# relayboard.net
KiCad netlist of a schematic drawn in EAGLE
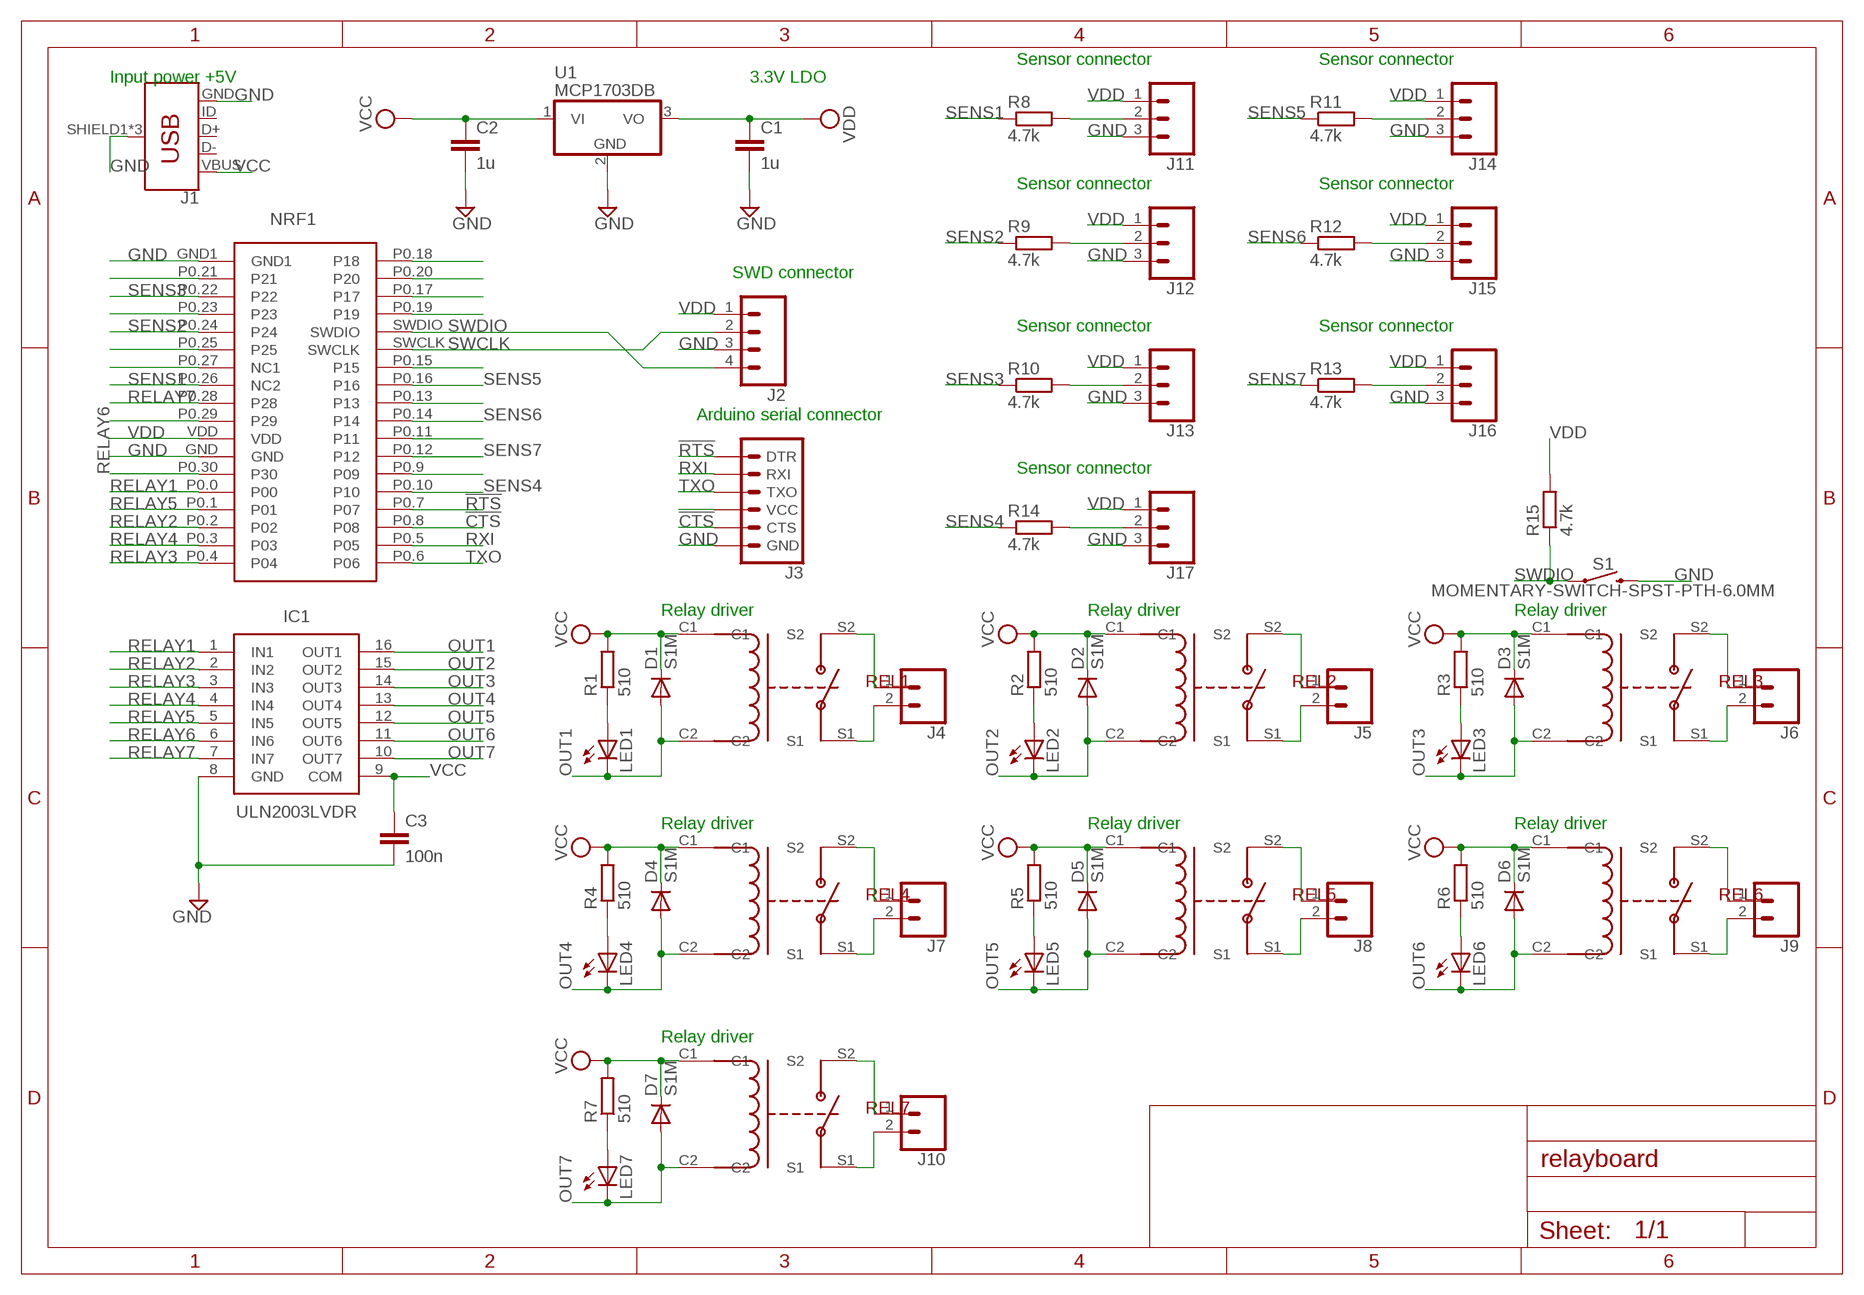
[diagram p0: schematic, sheet 1]

(export (version "E")
  (design (tool "Eeschema 10.0.6"))
  (components
    (comp (ref "C1")
      (value "1u")
      (footprint "eagle-import:C0805")
      (libsource (lib "eagle-import") (part "C-EUC0805"))
    )
    (comp (ref "C2")
      (value "1u")
      (footprint "eagle-import:C0805")
      (libsource (lib "eagle-import") (part "C-EUC0805"))
    )
    (comp (ref "C3")
      (value "100n")
      (footprint "eagle-import:C0805")
      (libsource (lib "eagle-import") (part "C-EUC0805"))
    )
    (comp (ref "D1")
      (value "S1M")
      (footprint "eagle-import:SMA")
      (libsource (lib "eagle-import") (part "S1M"))
    )
    (comp (ref "D2")
      (value "S1M")
      (footprint "eagle-import:SMA")
      (libsource (lib "eagle-import") (part "S1M"))
    )
    (comp (ref "D3")
      (value "S1M")
      (footprint "eagle-import:SMA")
      (libsource (lib "eagle-import") (part "S1M"))
    )
    (comp (ref "D4")
      (value "S1M")
      (footprint "eagle-import:SMA")
      (libsource (lib "eagle-import") (part "S1M"))
    )
    (comp (ref "D5")
      (value "S1M")
      (footprint "eagle-import:SMA")
      (libsource (lib "eagle-import") (part "S1M"))
    )
    (comp (ref "D6")
      (value "S1M")
      (footprint "eagle-import:SMA")
      (libsource (lib "eagle-import") (part "S1M"))
    )
    (comp (ref "D7")
      (value "S1M")
      (footprint "eagle-import:SMA")
      (libsource (lib "eagle-import") (part "S1M"))
    )
    (comp (ref "IC1")
      (value "ULN2003LVDR")
      (footprint "eagle-import:SOIC127P600X175-16N")
      (fields (field (name "RS_PART_NUMBER") "8095475"))
      (libsource (lib "eagle-import") (part "ULN2003LVDR"))
    )
    (comp (ref "J1")
      (value "USB_MICRO-B_FEMALE-SMT")
      (footprint "eagle-import:USB-B-MICRO-SMD")
      (libsource (lib "eagle-import") (part "USB_MICRO-B_FEMALE-SMT"))
    )
    (comp (ref "J2")
      (value "CONN_04")
      (footprint "eagle-import:1X04")
      (libsource (lib "eagle-import") (part "CONN_04"))
    )
    (comp (ref "J3")
      (value "6_PIN_SERIAL_TARGET")
      (footprint "eagle-import:1X06")
      (libsource (lib "eagle-import") (part "6_PIN_SERIAL_TARGET"))
    )
    (comp (ref "J4")
      (value "CONN_025MM")
      (footprint "eagle-import:SCREWTERMINAL-5MM-2")
      (libsource (lib "eagle-import") (part "CONN_025MM"))
    )
    (comp (ref "J5")
      (value "CONN_025MM")
      (footprint "eagle-import:SCREWTERMINAL-5MM-2")
      (libsource (lib "eagle-import") (part "CONN_025MM"))
    )
    (comp (ref "J6")
      (value "CONN_025MM")
      (footprint "eagle-import:SCREWTERMINAL-5MM-2")
      (libsource (lib "eagle-import") (part "CONN_025MM"))
    )
    (comp (ref "J7")
      (value "CONN_025MM")
      (footprint "eagle-import:SCREWTERMINAL-5MM-2")
      (libsource (lib "eagle-import") (part "CONN_025MM"))
    )
    (comp (ref "J8")
      (value "CONN_025MM")
      (footprint "eagle-import:SCREWTERMINAL-5MM-2")
      (libsource (lib "eagle-import") (part "CONN_025MM"))
    )
    (comp (ref "J9")
      (value "CONN_025MM")
      (footprint "eagle-import:SCREWTERMINAL-5MM-2")
      (libsource (lib "eagle-import") (part "CONN_025MM"))
    )
    (comp (ref "J10")
      (value "CONN_025MM")
      (footprint "eagle-import:SCREWTERMINAL-5MM-2")
      (libsource (lib "eagle-import") (part "CONN_025MM"))
    )
    (comp (ref "J11")
      (value "CONN_03SCREW")
      (footprint "eagle-import:SCREWTERMINAL-3.5MM-3")
      (libsource (lib "eagle-import") (part "CONN_03SCREW"))
    )
    (comp (ref "J12")
      (value "CONN_03SCREW")
      (footprint "eagle-import:SCREWTERMINAL-3.5MM-3")
      (libsource (lib "eagle-import") (part "CONN_03SCREW"))
    )
    (comp (ref "J13")
      (value "CONN_03SCREW")
      (footprint "eagle-import:SCREWTERMINAL-3.5MM-3")
      (libsource (lib "eagle-import") (part "CONN_03SCREW"))
    )
    (comp (ref "J14")
      (value "CONN_03SCREW")
      (footprint "eagle-import:SCREWTERMINAL-3.5MM-3")
      (libsource (lib "eagle-import") (part "CONN_03SCREW"))
    )
    (comp (ref "J15")
      (value "CONN_03SCREW")
      (footprint "eagle-import:SCREWTERMINAL-3.5MM-3")
      (libsource (lib "eagle-import") (part "CONN_03SCREW"))
    )
    (comp (ref "J16")
      (value "CONN_03SCREW")
      (footprint "eagle-import:SCREWTERMINAL-3.5MM-3")
      (libsource (lib "eagle-import") (part "CONN_03SCREW"))
    )
    (comp (ref "J17")
      (value "CONN_03SCREW")
      (footprint "eagle-import:SCREWTERMINAL-3.5MM-3")
      (libsource (lib "eagle-import") (part "CONN_03SCREW"))
    )
    (comp (ref "LED1")
      (value "LEDSML1206")
      (footprint "eagle-import:SML1206")
      (libsource (lib "eagle-import") (part "LEDSML1206"))
    )
    (comp (ref "LED2")
      (value "LEDSML1206")
      (footprint "eagle-import:SML1206")
      (libsource (lib "eagle-import") (part "LEDSML1206"))
    )
    (comp (ref "LED3")
      (value "LEDSML1206")
      (footprint "eagle-import:SML1206")
      (libsource (lib "eagle-import") (part "LEDSML1206"))
    )
    (comp (ref "LED4")
      (value "LEDSML1206")
      (footprint "eagle-import:SML1206")
      (libsource (lib "eagle-import") (part "LEDSML1206"))
    )
    (comp (ref "LED5")
      (value "LEDSML1206")
      (footprint "eagle-import:SML1206")
      (libsource (lib "eagle-import") (part "LEDSML1206"))
    )
    (comp (ref "LED6")
      (value "LEDSML1206")
      (footprint "eagle-import:SML1206")
      (libsource (lib "eagle-import") (part "LEDSML1206"))
    )
    (comp (ref "LED7")
      (value "LEDSML1206")
      (footprint "eagle-import:SML1206")
      (libsource (lib "eagle-import") (part "LEDSML1206"))
    )
    (comp (ref "NRF1")
      (value "NRF51822MODULE")
      (footprint "eagle-import:NRF")
      (libsource (lib "eagle-import") (part "NRF51822MODULE"))
    )
    (comp (ref "R1")
      (value "510")
      (footprint "eagle-import:R0603")
      (libsource (lib "eagle-import") (part "R-EU_R0603"))
    )
    (comp (ref "R2")
      (value "510")
      (footprint "eagle-import:R0603")
      (libsource (lib "eagle-import") (part "R-EU_R0603"))
    )
    (comp (ref "R3")
      (value "510")
      (footprint "eagle-import:R0603")
      (libsource (lib "eagle-import") (part "R-EU_R0603"))
    )
    (comp (ref "R4")
      (value "510")
      (footprint "eagle-import:R0603")
      (libsource (lib "eagle-import") (part "R-EU_R0603"))
    )
    (comp (ref "R5")
      (value "510")
      (footprint "eagle-import:R0603")
      (libsource (lib "eagle-import") (part "R-EU_R0603"))
    )
    (comp (ref "R6")
      (value "510")
      (footprint "eagle-import:R0603")
      (libsource (lib "eagle-import") (part "R-EU_R0603"))
    )
    (comp (ref "R7")
      (value "510")
      (footprint "eagle-import:R0603")
      (libsource (lib "eagle-import") (part "R-EU_R0603"))
    )
    (comp (ref "R8")
      (value "4.7k")
      (footprint "eagle-import:R0603")
      (libsource (lib "eagle-import") (part "R-EU_R0603"))
    )
    (comp (ref "R9")
      (value "4.7k")
      (footprint "eagle-import:R0603")
      (libsource (lib "eagle-import") (part "R-EU_R0603"))
    )
    (comp (ref "R10")
      (value "4.7k")
      (footprint "eagle-import:R0603")
      (libsource (lib "eagle-import") (part "R-EU_R0603"))
    )
    (comp (ref "R11")
      (value "4.7k")
      (footprint "eagle-import:R0603")
      (libsource (lib "eagle-import") (part "R-EU_R0603"))
    )
    (comp (ref "R12")
      (value "4.7k")
      (footprint "eagle-import:R0603")
      (libsource (lib "eagle-import") (part "R-EU_R0603"))
    )
    (comp (ref "R13")
      (value "4.7k")
      (footprint "eagle-import:R0603")
      (libsource (lib "eagle-import") (part "R-EU_R0603"))
    )
    (comp (ref "R14")
      (value "4.7k")
      (footprint "eagle-import:R0603")
      (libsource (lib "eagle-import") (part "R-EU_R0603"))
    )
    (comp (ref "R15")
      (value "4.7k")
      (footprint "eagle-import:R0603")
      (libsource (lib "eagle-import") (part "R-EU_R0603"))
    )
    (comp (ref "REL1")
      (value "NY5WK")
      (footprint "eagle-import:NY5WK")
      (libsource (lib "eagle-import") (part "NY5WK"))
    )
    (comp (ref "REL2")
      (value "NY5WK")
      (footprint "eagle-import:NY5WK")
      (libsource (lib "eagle-import") (part "NY5WK"))
    )
    (comp (ref "REL3")
      (value "NY5WK")
      (footprint "eagle-import:NY5WK")
      (libsource (lib "eagle-import") (part "NY5WK"))
    )
    (comp (ref "REL4")
      (value "NY5WK")
      (footprint "eagle-import:NY5WK")
      (libsource (lib "eagle-import") (part "NY5WK"))
    )
    (comp (ref "REL5")
      (value "NY5WK")
      (footprint "eagle-import:NY5WK")
      (libsource (lib "eagle-import") (part "NY5WK"))
    )
    (comp (ref "REL6")
      (value "NY5WK")
      (footprint "eagle-import:NY5WK")
      (libsource (lib "eagle-import") (part "NY5WK"))
    )
    (comp (ref "REL7")
      (value "NY5WK")
      (footprint "eagle-import:NY5WK")
      (libsource (lib "eagle-import") (part "NY5WK"))
    )
    (comp (ref "S1")
      (value "MOMENTARY-SWITCH-SPST-PTH-6.0MM")
      (footprint "eagle-import:TACTILE_SWITCH_PTH_6.0MM")
      (libsource (lib "eagle-import") (part "MOMENTARY-SWITCH-SPST-PTH-6.0MM"))
    )
    (comp (ref "U1")
      (value "MCP1703DB")
      (footprint "eagle-import:SOT223")
      (libsource (lib "eagle-import") (part "MCP1703DB"))
    )
  )
  (nets
    (net (code "1") (name "/OUT1") (class "Default")
      (node (ref "D1") (pin "A") (pinfunction "A_A") (pintype "passive"))
      (node (ref "IC1") (pin "16") (pinfunction "OUT1_16") (pintype "input"))
      (node (ref "LED1") (pin "C") (pinfunction "C_C") (pintype "passive"))
      (node (ref "REL1") (pin "C2") (pinfunction "C2_C2") (pintype "bidirectional"))
    )
    (net (code "2") (name "/OUT2") (class "Default")
      (node (ref "D2") (pin "A") (pinfunction "A_A") (pintype "passive"))
      (node (ref "IC1") (pin "15") (pinfunction "OUT2_15") (pintype "input"))
      (node (ref "LED2") (pin "C") (pinfunction "C_C") (pintype "passive"))
      (node (ref "REL2") (pin "C2") (pinfunction "C2_C2") (pintype "bidirectional"))
    )
    (net (code "3") (name "/OUT3") (class "Default")
      (node (ref "D3") (pin "A") (pinfunction "A_A") (pintype "passive"))
      (node (ref "IC1") (pin "14") (pinfunction "OUT3_14") (pintype "input"))
      (node (ref "LED3") (pin "C") (pinfunction "C_C") (pintype "passive"))
      (node (ref "REL3") (pin "C2") (pinfunction "C2_C2") (pintype "bidirectional"))
    )
    (net (code "4") (name "/OUT4") (class "Default")
      (node (ref "D4") (pin "A") (pinfunction "A_A") (pintype "passive"))
      (node (ref "IC1") (pin "13") (pinfunction "OUT4_13") (pintype "input"))
      (node (ref "LED4") (pin "C") (pinfunction "C_C") (pintype "passive"))
      (node (ref "REL4") (pin "C2") (pinfunction "C2_C2") (pintype "bidirectional"))
    )
    (net (code "5") (name "/OUT5") (class "Default")
      (node (ref "D5") (pin "A") (pinfunction "A_A") (pintype "passive"))
      (node (ref "IC1") (pin "12") (pinfunction "OUT5_12") (pintype "input"))
      (node (ref "LED5") (pin "C") (pinfunction "C_C") (pintype "passive"))
      (node (ref "REL5") (pin "C2") (pinfunction "C2_C2") (pintype "bidirectional"))
    )
    (net (code "6") (name "/OUT6") (class "Default")
      (node (ref "D6") (pin "A") (pinfunction "A_A") (pintype "passive"))
      (node (ref "IC1") (pin "11") (pinfunction "OUT6_11") (pintype "input"))
      (node (ref "LED6") (pin "C") (pinfunction "C_C") (pintype "passive"))
      (node (ref "REL6") (pin "C2") (pinfunction "C2_C2") (pintype "bidirectional"))
    )
    (net (code "7") (name "/OUT7") (class "Default")
      (node (ref "D7") (pin "A") (pinfunction "A_A") (pintype "passive"))
      (node (ref "IC1") (pin "10") (pinfunction "OUT7_10") (pintype "input"))
      (node (ref "LED7") (pin "C") (pinfunction "C_C") (pintype "passive"))
      (node (ref "REL7") (pin "C2") (pinfunction "C2_C2") (pintype "bidirectional"))
    )
    (net (code "8") (name "/RELAY1") (class "Default")
      (node (ref "IC1") (pin "1") (pinfunction "IN1_1") (pintype "input"))
      (node (ref "NRF1") (pin "P0.0") (pinfunction "P00_P0.0") (pintype "bidirectional"))
    )
    (net (code "9") (name "/RELAY2") (class "Default")
      (node (ref "IC1") (pin "2") (pinfunction "IN2_2") (pintype "input"))
      (node (ref "NRF1") (pin "P0.2") (pinfunction "P02_P0.2") (pintype "bidirectional"))
    )
    (net (code "10") (name "/RELAY3") (class "Default")
      (node (ref "IC1") (pin "3") (pinfunction "IN3_3") (pintype "input"))
      (node (ref "NRF1") (pin "P0.4") (pinfunction "P04_P0.4") (pintype "bidirectional"))
    )
    (net (code "11") (name "/RELAY4") (class "Default")
      (node (ref "IC1") (pin "4") (pinfunction "IN4_4") (pintype "input"))
      (node (ref "NRF1") (pin "P0.3") (pinfunction "P03_P0.3") (pintype "bidirectional"))
    )
    (net (code "12") (name "/RELAY5") (class "Default")
      (node (ref "IC1") (pin "5") (pinfunction "IN5_5") (pintype "input"))
      (node (ref "NRF1") (pin "P0.1") (pinfunction "P01_P0.1") (pintype "bidirectional"))
    )
    (net (code "13") (name "/RELAY6") (class "Default")
      (node (ref "IC1") (pin "6") (pinfunction "IN6_6") (pintype "input"))
      (node (ref "NRF1") (pin "P0.30") (pinfunction "P30_P0.30") (pintype "bidirectional"))
    )
    (net (code "14") (name "/RELAY7") (class "Default")
      (node (ref "IC1") (pin "7") (pinfunction "IN7_7") (pintype "input"))
      (node (ref "NRF1") (pin "P0.28") (pinfunction "P28_P0.28") (pintype "bidirectional"))
    )
    (net (code "15") (name "/RXI") (class "Default")
      (node (ref "J3") (pin "2") (pinfunction "RXI_2") (pintype "passive"))
      (node (ref "NRF1") (pin "P0.5") (pinfunction "P05_P0.5") (pintype "bidirectional"))
    )
    (net (code "16") (name "/SENS1") (class "Default")
      (node (ref "NRF1") (pin "P0.26") (pinfunction "NC2_P0.26") (pintype "bidirectional"))
      (node (ref "R8") (pin "1") (pinfunction "1_1") (pintype "passive"))
    )
    (net (code "17") (name "/SENS2") (class "Default")
      (node (ref "NRF1") (pin "P0.24") (pinfunction "P24_P0.24") (pintype "bidirectional"))
      (node (ref "R9") (pin "1") (pinfunction "1_1") (pintype "passive"))
    )
    (net (code "18") (name "/SENS3") (class "Default")
      (node (ref "NRF1") (pin "P0.22") (pinfunction "P22_P0.22") (pintype "bidirectional"))
      (node (ref "R10") (pin "1") (pinfunction "1_1") (pintype "passive"))
    )
    (net (code "19") (name "/SENS4") (class "Default")
      (node (ref "NRF1") (pin "P0.10") (pinfunction "P10_P0.10") (pintype "bidirectional"))
      (node (ref "R14") (pin "1") (pinfunction "1_1") (pintype "passive"))
    )
    (net (code "20") (name "/SENS5") (class "Default")
      (node (ref "NRF1") (pin "P0.16") (pinfunction "P16_P0.16") (pintype "bidirectional"))
      (node (ref "R11") (pin "1") (pinfunction "1_1") (pintype "passive"))
    )
    (net (code "21") (name "/SENS6") (class "Default")
      (node (ref "NRF1") (pin "P0.14") (pinfunction "P14_P0.14") (pintype "bidirectional"))
      (node (ref "R12") (pin "1") (pinfunction "1_1") (pintype "passive"))
    )
    (net (code "22") (name "/SENS7") (class "Default")
      (node (ref "NRF1") (pin "P0.12") (pinfunction "P12_P0.12") (pintype "bidirectional"))
      (node (ref "R13") (pin "1") (pinfunction "1_1") (pintype "passive"))
    )
    (net (code "23") (name "/SWCLK") (class "Default")
      (node (ref "J2") (pin "2") (pinfunction "2_2") (pintype "passive"))
      (node (ref "NRF1") (pin "SWCLK") (pinfunction "SWCLK_SWCLK") (pintype "bidirectional"))
    )
    (net (code "24") (name "/SWDIO") (class "Default")
      (node (ref "J2") (pin "4") (pinfunction "4_4") (pintype "passive"))
      (node (ref "NRF1") (pin "SWDIO") (pinfunction "SWDIO_SWDIO") (pintype "bidirectional"))
      (node (ref "R15") (pin "1") (pinfunction "1_1") (pintype "passive"))
      (node (ref "S1") (pin "1") (pinfunction "1_1") (pintype "passive"))
    )
    (net (code "25") (name "/TXO") (class "Default")
      (node (ref "J3") (pin "3") (pinfunction "TXO_3") (pintype "passive"))
      (node (ref "NRF1") (pin "P0.6") (pinfunction "P06_P0.6") (pintype "bidirectional"))
    )
    (net (code "26") (name "/~{CTS}") (class "Default")
      (node (ref "J3") (pin "5") (pinfunction "CTS_5") (pintype "passive"))
      (node (ref "NRF1") (pin "P0.8") (pinfunction "P08_P0.8") (pintype "bidirectional"))
    )
    (net (code "27") (name "/~{RTS}") (class "Default")
      (node (ref "J3") (pin "1") (pinfunction "DTR_1") (pintype "passive"))
      (node (ref "NRF1") (pin "P0.7") (pinfunction "P07_P0.7") (pintype "bidirectional"))
    )
    (net (code "28") (name "GND") (class "Default")
      (node (ref "C1") (pin "2") (pinfunction "2_2") (pintype "passive"))
      (node (ref "C2") (pin "2") (pinfunction "2_2") (pintype "passive"))
      (node (ref "C3") (pin "2") (pinfunction "2_2") (pintype "passive"))
      (node (ref "IC1") (pin "8") (pinfunction "GND_8") (pintype "input"))
      (node (ref "J1") (pin "GND") (pinfunction "GND_GND") (pintype "power_in"))
      (node (ref "J1") (pin "SHIELD1") (pinfunction "SHIELD_SHIELD1") (pintype "bidirectional"))
      (node (ref "J1") (pin "SHIELD2") (pinfunction "SHIELD_SHIELD2") (pintype "bidirectional"))
      (node (ref "J1") (pin "SHIELD3") (pinfunction "SHIELD_SHIELD3") (pintype "bidirectional"))
      (node (ref "J11") (pin "3") (pinfunction "3_3") (pintype "passive"))
      (node (ref "J12") (pin "3") (pinfunction "3_3") (pintype "passive"))
      (node (ref "J13") (pin "3") (pinfunction "3_3") (pintype "passive"))
      (node (ref "J14") (pin "3") (pinfunction "3_3") (pintype "passive"))
      (node (ref "J15") (pin "3") (pinfunction "3_3") (pintype "passive"))
      (node (ref "J16") (pin "3") (pinfunction "3_3") (pintype "passive"))
      (node (ref "J17") (pin "3") (pinfunction "3_3") (pintype "passive"))
      (node (ref "J2") (pin "3") (pinfunction "3_3") (pintype "passive"))
      (node (ref "J3") (pin "6") (pinfunction "GND_6") (pintype "passive"))
      (node (ref "NRF1") (pin "GND") (pinfunction "GND_GND") (pintype "bidirectional"))
      (node (ref "NRF1") (pin "GND1") (pinfunction "GND1_GND1") (pintype "bidirectional"))
      (node (ref "S1") (pin "3") (pinfunction "2_3") (pintype "passive"))
      (node (ref "U1") (pin "2") (pinfunction "GND_2") (pintype "passive"))
    )
    (net (code "29") (name "Net-(J4-Pad1)") (class "Default")
      (node (ref "J4") (pin "1") (pinfunction "1_1") (pintype "passive"))
      (node (ref "REL1") (pin "S2") (pinfunction "S2_S2") (pintype "bidirectional"))
    )
    (net (code "30") (name "Net-(J4-Pad2)") (class "Default")
      (node (ref "J4") (pin "2") (pinfunction "2_2") (pintype "passive"))
      (node (ref "REL1") (pin "S1") (pinfunction "S1_S1") (pintype "bidirectional"))
    )
    (net (code "31") (name "Net-(J5-Pad1)") (class "Default")
      (node (ref "J5") (pin "1") (pinfunction "1_1") (pintype "passive"))
      (node (ref "REL2") (pin "S2") (pinfunction "S2_S2") (pintype "bidirectional"))
    )
    (net (code "32") (name "Net-(J5-Pad2)") (class "Default")
      (node (ref "J5") (pin "2") (pinfunction "2_2") (pintype "passive"))
      (node (ref "REL2") (pin "S1") (pinfunction "S1_S1") (pintype "bidirectional"))
    )
    (net (code "33") (name "Net-(J6-Pad1)") (class "Default")
      (node (ref "J6") (pin "1") (pinfunction "1_1") (pintype "passive"))
      (node (ref "REL3") (pin "S2") (pinfunction "S2_S2") (pintype "bidirectional"))
    )
    (net (code "34") (name "Net-(J6-Pad2)") (class "Default")
      (node (ref "J6") (pin "2") (pinfunction "2_2") (pintype "passive"))
      (node (ref "REL3") (pin "S1") (pinfunction "S1_S1") (pintype "bidirectional"))
    )
    (net (code "35") (name "Net-(J7-Pad1)") (class "Default")
      (node (ref "J7") (pin "1") (pinfunction "1_1") (pintype "passive"))
      (node (ref "REL4") (pin "S2") (pinfunction "S2_S2") (pintype "bidirectional"))
    )
    (net (code "36") (name "Net-(J7-Pad2)") (class "Default")
      (node (ref "J7") (pin "2") (pinfunction "2_2") (pintype "passive"))
      (node (ref "REL4") (pin "S1") (pinfunction "S1_S1") (pintype "bidirectional"))
    )
    (net (code "37") (name "Net-(J8-Pad1)") (class "Default")
      (node (ref "J8") (pin "1") (pinfunction "1_1") (pintype "passive"))
      (node (ref "REL5") (pin "S2") (pinfunction "S2_S2") (pintype "bidirectional"))
    )
    (net (code "38") (name "Net-(J8-Pad2)") (class "Default")
      (node (ref "J8") (pin "2") (pinfunction "2_2") (pintype "passive"))
      (node (ref "REL5") (pin "S1") (pinfunction "S1_S1") (pintype "bidirectional"))
    )
    (net (code "39") (name "Net-(J9-Pad1)") (class "Default")
      (node (ref "J9") (pin "1") (pinfunction "1_1") (pintype "passive"))
      (node (ref "REL6") (pin "S2") (pinfunction "S2_S2") (pintype "bidirectional"))
    )
    (net (code "40") (name "Net-(J9-Pad2)") (class "Default")
      (node (ref "J9") (pin "2") (pinfunction "2_2") (pintype "passive"))
      (node (ref "REL6") (pin "S1") (pinfunction "S1_S1") (pintype "bidirectional"))
    )
    (net (code "41") (name "Net-(J10-Pad1)") (class "Default")
      (node (ref "J10") (pin "1") (pinfunction "1_1") (pintype "passive"))
      (node (ref "REL7") (pin "S2") (pinfunction "S2_S2") (pintype "bidirectional"))
    )
    (net (code "42") (name "Net-(J10-Pad2)") (class "Default")
      (node (ref "J10") (pin "2") (pinfunction "2_2") (pintype "passive"))
      (node (ref "REL7") (pin "S1") (pinfunction "S1_S1") (pintype "bidirectional"))
    )
    (net (code "43") (name "Net-(J11-Pad2)") (class "Default")
      (node (ref "J11") (pin "2") (pinfunction "2_2") (pintype "passive"))
      (node (ref "R8") (pin "2") (pinfunction "2_2") (pintype "passive"))
    )
    (net (code "44") (name "Net-(J12-Pad2)") (class "Default")
      (node (ref "J12") (pin "2") (pinfunction "2_2") (pintype "passive"))
      (node (ref "R9") (pin "2") (pinfunction "2_2") (pintype "passive"))
    )
    (net (code "45") (name "Net-(J13-Pad2)") (class "Default")
      (node (ref "J13") (pin "2") (pinfunction "2_2") (pintype "passive"))
      (node (ref "R10") (pin "2") (pinfunction "2_2") (pintype "passive"))
    )
    (net (code "46") (name "Net-(J14-Pad2)") (class "Default")
      (node (ref "J14") (pin "2") (pinfunction "2_2") (pintype "passive"))
      (node (ref "R11") (pin "2") (pinfunction "2_2") (pintype "passive"))
    )
    (net (code "47") (name "Net-(J15-Pad2)") (class "Default")
      (node (ref "J15") (pin "2") (pinfunction "2_2") (pintype "passive"))
      (node (ref "R12") (pin "2") (pinfunction "2_2") (pintype "passive"))
    )
    (net (code "48") (name "Net-(J16-Pad2)") (class "Default")
      (node (ref "J16") (pin "2") (pinfunction "2_2") (pintype "passive"))
      (node (ref "R13") (pin "2") (pinfunction "2_2") (pintype "passive"))
    )
    (net (code "49") (name "Net-(J17-Pad2)") (class "Default")
      (node (ref "J17") (pin "2") (pinfunction "2_2") (pintype "passive"))
      (node (ref "R14") (pin "2") (pinfunction "2_2") (pintype "passive"))
    )
    (net (code "50") (name "Net-(LED1-PadA)") (class "Default")
      (node (ref "LED1") (pin "A") (pinfunction "A_A") (pintype "passive"))
      (node (ref "R1") (pin "1") (pinfunction "1_1") (pintype "passive"))
    )
    (net (code "51") (name "Net-(LED2-PadA)") (class "Default")
      (node (ref "LED2") (pin "A") (pinfunction "A_A") (pintype "passive"))
      (node (ref "R2") (pin "1") (pinfunction "1_1") (pintype "passive"))
    )
    (net (code "52") (name "Net-(LED3-PadA)") (class "Default")
      (node (ref "LED3") (pin "A") (pinfunction "A_A") (pintype "passive"))
      (node (ref "R3") (pin "1") (pinfunction "1_1") (pintype "passive"))
    )
    (net (code "53") (name "Net-(LED4-PadA)") (class "Default")
      (node (ref "LED4") (pin "A") (pinfunction "A_A") (pintype "passive"))
      (node (ref "R4") (pin "1") (pinfunction "1_1") (pintype "passive"))
    )
    (net (code "54") (name "Net-(LED5-PadA)") (class "Default")
      (node (ref "LED5") (pin "A") (pinfunction "A_A") (pintype "passive"))
      (node (ref "R5") (pin "1") (pinfunction "1_1") (pintype "passive"))
    )
    (net (code "55") (name "Net-(LED6-PadA)") (class "Default")
      (node (ref "LED6") (pin "A") (pinfunction "A_A") (pintype "passive"))
      (node (ref "R6") (pin "1") (pinfunction "1_1") (pintype "passive"))
    )
    (net (code "56") (name "Net-(LED7-PadA)") (class "Default")
      (node (ref "LED7") (pin "A") (pinfunction "A_A") (pintype "passive"))
      (node (ref "R7") (pin "1") (pinfunction "1_1") (pintype "passive"))
    )
    (net (code "57") (name "VCC") (class "Default")
      (node (ref "C2") (pin "1") (pinfunction "1_1") (pintype "passive"))
      (node (ref "C3") (pin "1") (pinfunction "1_1") (pintype "passive"))
      (node (ref "D1") (pin "C") (pinfunction "C_C") (pintype "passive"))
      (node (ref "D2") (pin "C") (pinfunction "C_C") (pintype "passive"))
      (node (ref "D3") (pin "C") (pinfunction "C_C") (pintype "passive"))
      (node (ref "D4") (pin "C") (pinfunction "C_C") (pintype "passive"))
      (node (ref "D5") (pin "C") (pinfunction "C_C") (pintype "passive"))
      (node (ref "D6") (pin "C") (pinfunction "C_C") (pintype "passive"))
      (node (ref "D7") (pin "C") (pinfunction "C_C") (pintype "passive"))
      (node (ref "IC1") (pin "9") (pinfunction "COM_9") (pintype "input"))
      (node (ref "J1") (pin "VBUS") (pinfunction "VBUS_VBUS") (pintype "power_in"))
      (node (ref "R1") (pin "2") (pinfunction "2_2") (pintype "passive"))
      (node (ref "R2") (pin "2") (pinfunction "2_2") (pintype "passive"))
      (node (ref "R3") (pin "2") (pinfunction "2_2") (pintype "passive"))
      (node (ref "R4") (pin "2") (pinfunction "2_2") (pintype "passive"))
      (node (ref "R5") (pin "2") (pinfunction "2_2") (pintype "passive"))
      (node (ref "R6") (pin "2") (pinfunction "2_2") (pintype "passive"))
      (node (ref "R7") (pin "2") (pinfunction "2_2") (pintype "passive"))
      (node (ref "REL1") (pin "C1") (pinfunction "C1_C1") (pintype "bidirectional"))
      (node (ref "REL2") (pin "C1") (pinfunction "C1_C1") (pintype "bidirectional"))
      (node (ref "REL3") (pin "C1") (pinfunction "C1_C1") (pintype "bidirectional"))
      (node (ref "REL4") (pin "C1") (pinfunction "C1_C1") (pintype "bidirectional"))
      (node (ref "REL5") (pin "C1") (pinfunction "C1_C1") (pintype "bidirectional"))
      (node (ref "REL6") (pin "C1") (pinfunction "C1_C1") (pintype "bidirectional"))
      (node (ref "REL7") (pin "C1") (pinfunction "C1_C1") (pintype "bidirectional"))
      (node (ref "U1") (pin "1") (pinfunction "VI_1") (pintype "input"))
    )
    (net (code "58") (name "VDD") (class "Default")
      (node (ref "C1") (pin "1") (pinfunction "1_1") (pintype "passive"))
      (node (ref "J11") (pin "1") (pinfunction "1_1") (pintype "passive"))
      (node (ref "J12") (pin "1") (pinfunction "1_1") (pintype "passive"))
      (node (ref "J13") (pin "1") (pinfunction "1_1") (pintype "passive"))
      (node (ref "J14") (pin "1") (pinfunction "1_1") (pintype "passive"))
      (node (ref "J15") (pin "1") (pinfunction "1_1") (pintype "passive"))
      (node (ref "J16") (pin "1") (pinfunction "1_1") (pintype "passive"))
      (node (ref "J17") (pin "1") (pinfunction "1_1") (pintype "passive"))
      (node (ref "J2") (pin "1") (pinfunction "1_1") (pintype "passive"))
      (node (ref "NRF1") (pin "VDD") (pinfunction "VDD_VDD") (pintype "bidirectional"))
      (node (ref "R15") (pin "2") (pinfunction "2_2") (pintype "passive"))
      (node (ref "U1") (pin "3") (pinfunction "VO_3") (pintype "passive"))
    )
    (net (code "59") (name "unconnected-(J1-PadD+)") (class "Default")
      (node (ref "J1") (pin "D+") (pinfunction "D+_D+") (pintype "bidirectional"))
    )
    (net (code "60") (name "unconnected-(J1-PadD-)") (class "Default")
      (node (ref "J1") (pin "D-") (pinfunction "D-_D-") (pintype "bidirectional"))
    )
    (net (code "61") (name "unconnected-(J1-PadID)") (class "Default")
      (node (ref "J1") (pin "ID") (pinfunction "ID_ID") (pintype "bidirectional"))
    )
    (net (code "62") (name "unconnected-(J3-VCC-Pad4)") (class "Default")
      (node (ref "J3") (pin "4") (pinfunction "VCC_4") (pintype "passive"))
    )
    (net (code "63") (name "unconnected-(NRF1-NC1-PadP0.27)") (class "Default")
      (node (ref "NRF1") (pin "P0.27") (pinfunction "NC1_P0.27") (pintype "bidirectional"))
    )
    (net (code "64") (name "unconnected-(NRF1-P09-PadP0.9)") (class "Default")
      (node (ref "NRF1") (pin "P0.9") (pinfunction "P09_P0.9") (pintype "bidirectional"))
    )
    (net (code "65") (name "unconnected-(NRF1-P11-PadP0.11)") (class "Default")
      (node (ref "NRF1") (pin "P0.11") (pinfunction "P11_P0.11") (pintype "bidirectional"))
    )
    (net (code "66") (name "unconnected-(NRF1-P13-PadP0.13)") (class "Default")
      (node (ref "NRF1") (pin "P0.13") (pinfunction "P13_P0.13") (pintype "bidirectional"))
    )
    (net (code "67") (name "unconnected-(NRF1-P15-PadP0.15)") (class "Default")
      (node (ref "NRF1") (pin "P0.15") (pinfunction "P15_P0.15") (pintype "bidirectional"))
    )
    (net (code "68") (name "unconnected-(NRF1-P17-PadP0.17)") (class "Default")
      (node (ref "NRF1") (pin "P0.17") (pinfunction "P17_P0.17") (pintype "bidirectional"))
    )
    (net (code "69") (name "unconnected-(NRF1-P18-PadP0.18)") (class "Default")
      (node (ref "NRF1") (pin "P0.18") (pinfunction "P18_P0.18") (pintype "bidirectional"))
    )
    (net (code "70") (name "unconnected-(NRF1-P19-PadP0.19)") (class "Default")
      (node (ref "NRF1") (pin "P0.19") (pinfunction "P19_P0.19") (pintype "bidirectional"))
    )
    (net (code "71") (name "unconnected-(NRF1-P20-PadP0.20)") (class "Default")
      (node (ref "NRF1") (pin "P0.20") (pinfunction "P20_P0.20") (pintype "bidirectional"))
    )
    (net (code "72") (name "unconnected-(NRF1-P21-PadP0.21)") (class "Default")
      (node (ref "NRF1") (pin "P0.21") (pinfunction "P21_P0.21") (pintype "bidirectional"))
    )
    (net (code "73") (name "unconnected-(NRF1-P23-PadP0.23)") (class "Default")
      (node (ref "NRF1") (pin "P0.23") (pinfunction "P23_P0.23") (pintype "bidirectional"))
    )
    (net (code "74") (name "unconnected-(NRF1-P25-PadP0.25)") (class "Default")
      (node (ref "NRF1") (pin "P0.25") (pinfunction "P25_P0.25") (pintype "bidirectional"))
    )
    (net (code "75") (name "unconnected-(NRF1-P29-PadP0.29)") (class "Default")
      (node (ref "NRF1") (pin "P0.29") (pinfunction "P29_P0.29") (pintype "bidirectional"))
    )
  )
)
